# input3.net
KiCad netlist of a schematic drawn in Altium Designer
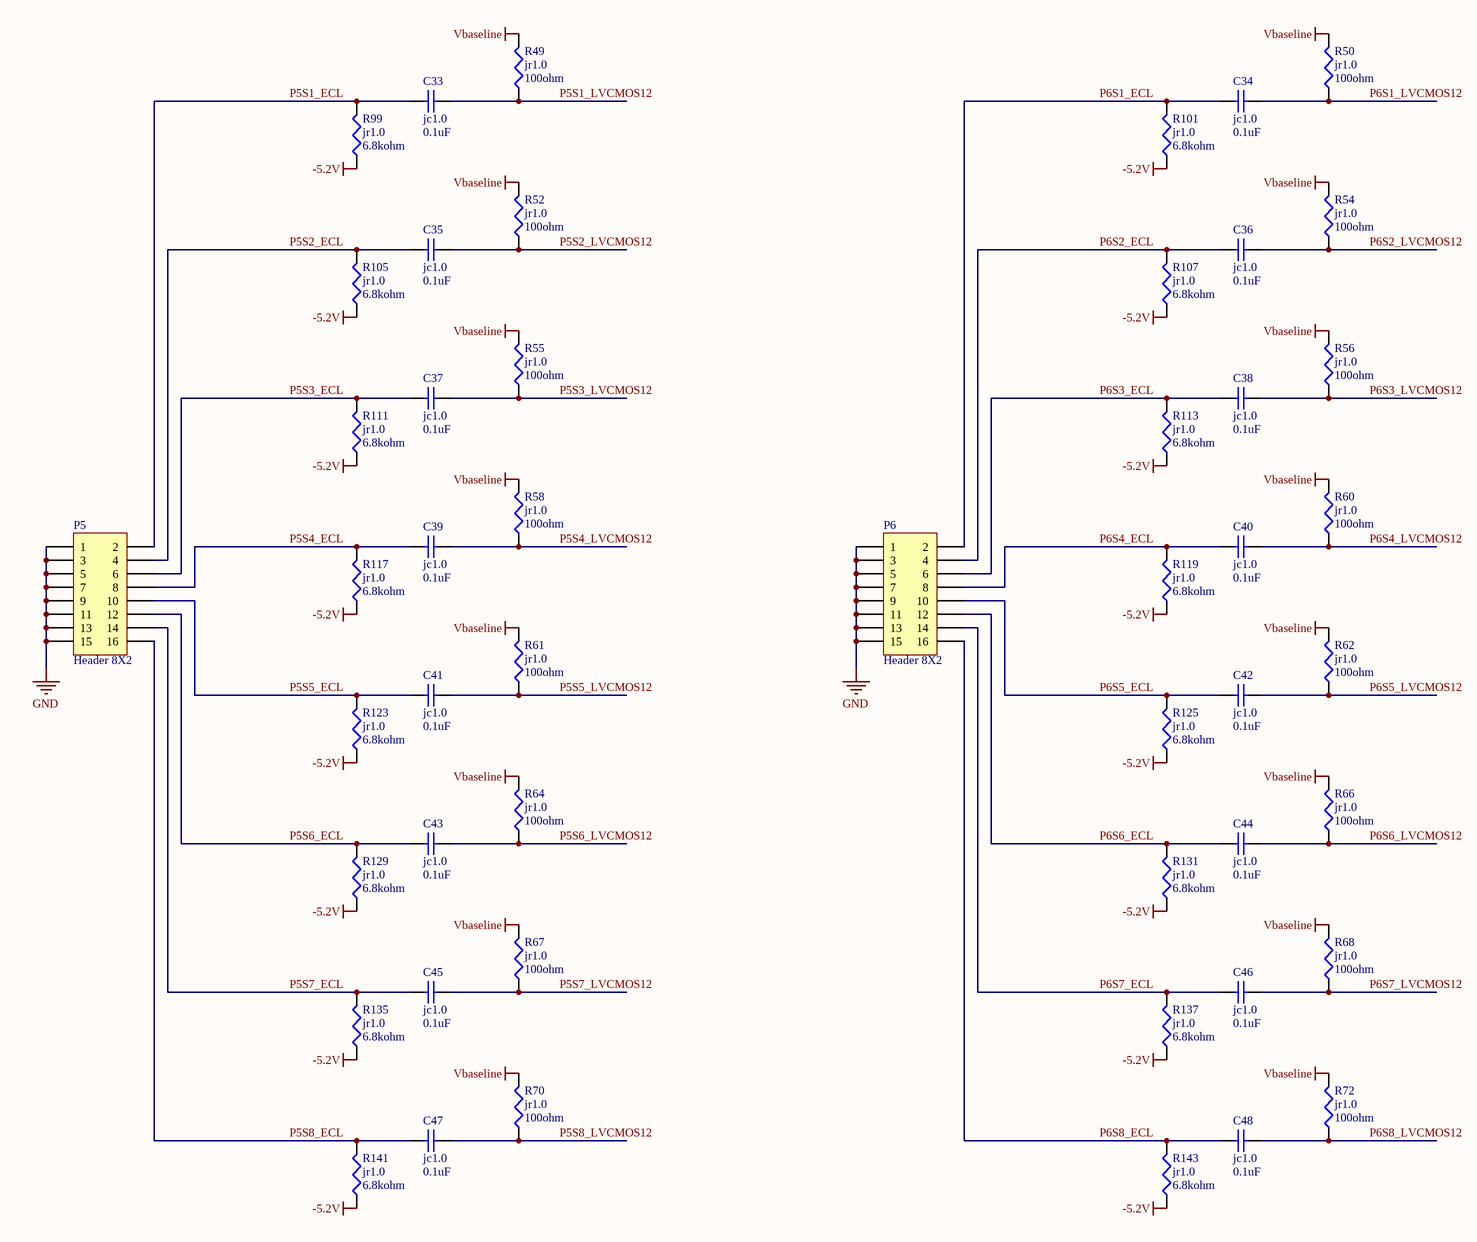
[diagram p0: input3.SchDoc]

(export (version "E")
  (design (tool "Eeschema 10.0.6"))
  (components
    (comp (ref "C33")
      (value "jc1.0")
      (footprint "0402")
      (description "Capacitor")
      (fields (field (name "ALTIUM_VALUE") "0.1uF") (field (name "PUBLISHER") "Altium Limited"))
      (libsource (lib "LIB01DXP2006SchLib") (part "Cap"))
    )
    (comp (ref "C34")
      (value "jc1.0")
      (footprint "0402")
      (description "Capacitor")
      (fields (field (name "ALTIUM_VALUE") "0.1uF") (field (name "PUBLISHER") "Altium Limited"))
      (libsource (lib "LIB01DXP2006SchLib") (part "Cap"))
    )
    (comp (ref "C35")
      (value "jc1.0")
      (footprint "0402")
      (description "Capacitor")
      (fields (field (name "ALTIUM_VALUE") "0.1uF") (field (name "PUBLISHER") "Altium Limited"))
      (libsource (lib "LIB01DXP2006SchLib") (part "Cap"))
    )
    (comp (ref "C36")
      (value "jc1.0")
      (footprint "0402")
      (description "Capacitor")
      (fields (field (name "ALTIUM_VALUE") "0.1uF") (field (name "PUBLISHER") "Altium Limited"))
      (libsource (lib "LIB01DXP2006SchLib") (part "Cap"))
    )
    (comp (ref "C37")
      (value "jc1.0")
      (footprint "0402")
      (description "Capacitor")
      (fields (field (name "ALTIUM_VALUE") "0.1uF") (field (name "PUBLISHER") "Altium Limited"))
      (libsource (lib "LIB01DXP2006SchLib") (part "Cap"))
    )
    (comp (ref "C38")
      (value "jc1.0")
      (footprint "0402")
      (description "Capacitor")
      (fields (field (name "ALTIUM_VALUE") "0.1uF") (field (name "PUBLISHER") "Altium Limited"))
      (libsource (lib "LIB01DXP2006SchLib") (part "Cap"))
    )
    (comp (ref "C39")
      (value "jc1.0")
      (footprint "0402")
      (description "Capacitor")
      (fields (field (name "ALTIUM_VALUE") "0.1uF") (field (name "PUBLISHER") "Altium Limited"))
      (libsource (lib "LIB01DXP2006SchLib") (part "Cap"))
    )
    (comp (ref "C40")
      (value "jc1.0")
      (footprint "0402")
      (description "Capacitor")
      (fields (field (name "ALTIUM_VALUE") "0.1uF") (field (name "PUBLISHER") "Altium Limited"))
      (libsource (lib "LIB01DXP2006SchLib") (part "Cap"))
    )
    (comp (ref "C41")
      (value "jc1.0")
      (footprint "0402")
      (description "Capacitor")
      (fields (field (name "ALTIUM_VALUE") "0.1uF") (field (name "PUBLISHER") "Altium Limited"))
      (libsource (lib "LIB01DXP2006SchLib") (part "Cap"))
    )
    (comp (ref "C42")
      (value "jc1.0")
      (footprint "0402")
      (description "Capacitor")
      (fields (field (name "ALTIUM_VALUE") "0.1uF") (field (name "PUBLISHER") "Altium Limited"))
      (libsource (lib "LIB01DXP2006SchLib") (part "Cap"))
    )
    (comp (ref "C43")
      (value "jc1.0")
      (footprint "0402")
      (description "Capacitor")
      (fields (field (name "ALTIUM_VALUE") "0.1uF") (field (name "PUBLISHER") "Altium Limited"))
      (libsource (lib "LIB01DXP2006SchLib") (part "Cap"))
    )
    (comp (ref "C44")
      (value "jc1.0")
      (footprint "0402")
      (description "Capacitor")
      (fields (field (name "ALTIUM_VALUE") "0.1uF") (field (name "PUBLISHER") "Altium Limited"))
      (libsource (lib "LIB01DXP2006SchLib") (part "Cap"))
    )
    (comp (ref "C45")
      (value "jc1.0")
      (footprint "0402")
      (description "Capacitor")
      (fields (field (name "ALTIUM_VALUE") "0.1uF") (field (name "PUBLISHER") "Altium Limited"))
      (libsource (lib "LIB01DXP2006SchLib") (part "Cap"))
    )
    (comp (ref "C46")
      (value "jc1.0")
      (footprint "0402")
      (description "Capacitor")
      (fields (field (name "ALTIUM_VALUE") "0.1uF") (field (name "PUBLISHER") "Altium Limited"))
      (libsource (lib "LIB01DXP2006SchLib") (part "Cap"))
    )
    (comp (ref "C47")
      (value "jc1.0")
      (footprint "0402")
      (description "Capacitor")
      (fields (field (name "ALTIUM_VALUE") "0.1uF") (field (name "PUBLISHER") "Altium Limited"))
      (libsource (lib "LIB01DXP2006SchLib") (part "Cap"))
    )
    (comp (ref "C48")
      (value "jc1.0")
      (footprint "0402")
      (description "Capacitor")
      (fields (field (name "ALTIUM_VALUE") "0.1uF") (field (name "PUBLISHER") "Altium Limited"))
      (libsource (lib "LIB01DXP2006SchLib") (part "Cap"))
    )
    (comp (ref "P5")
      (value "Header 8X2")
      (footprint "HDR2X8")
      (description "Header, 8-Pin, Dual row")
      (fields (field (name "PUBLISHER") "Altium Limited"))
      (libsource (lib "Miscellaneous Connectors") (part "Header 8X2"))
    )
    (comp (ref "P6")
      (value "Header 8X2")
      (footprint "HDR2X8")
      (description "Header, 8-Pin, Dual row")
      (fields (field (name "PUBLISHER") "Altium Limited"))
      (libsource (lib "Miscellaneous Connectors") (part "Header 8X2"))
    )
    (comp (ref "R49")
      (value "jr1.0")
      (footprint "0402")
      (description "Resistor")
      (fields (field (name "ALTIUM_VALUE") "100ohm") (field (name "PUBLISHER") "Altium Limited"))
      (libsource (lib "LIB01DXP2006SchLib") (part "Res"))
    )
    (comp (ref "R50")
      (value "jr1.0")
      (footprint "0402")
      (description "Resistor")
      (fields (field (name "ALTIUM_VALUE") "100ohm") (field (name "PUBLISHER") "Altium Limited"))
      (libsource (lib "LIB01DXP2006SchLib") (part "Res"))
    )
    (comp (ref "R52")
      (value "jr1.0")
      (footprint "0402")
      (description "Resistor")
      (fields (field (name "ALTIUM_VALUE") "100ohm") (field (name "PUBLISHER") "Altium Limited"))
      (libsource (lib "LIB01DXP2006SchLib") (part "Res"))
    )
    (comp (ref "R54")
      (value "jr1.0")
      (footprint "0402")
      (description "Resistor")
      (fields (field (name "ALTIUM_VALUE") "100ohm") (field (name "PUBLISHER") "Altium Limited"))
      (libsource (lib "LIB01DXP2006SchLib") (part "Res"))
    )
    (comp (ref "R55")
      (value "jr1.0")
      (footprint "0402")
      (description "Resistor")
      (fields (field (name "ALTIUM_VALUE") "100ohm") (field (name "PUBLISHER") "Altium Limited"))
      (libsource (lib "LIB01DXP2006SchLib") (part "Res"))
    )
    (comp (ref "R56")
      (value "jr1.0")
      (footprint "0402")
      (description "Resistor")
      (fields (field (name "ALTIUM_VALUE") "100ohm") (field (name "PUBLISHER") "Altium Limited"))
      (libsource (lib "LIB01DXP2006SchLib") (part "Res"))
    )
    (comp (ref "R58")
      (value "jr1.0")
      (footprint "0402")
      (description "Resistor")
      (fields (field (name "ALTIUM_VALUE") "100ohm") (field (name "PUBLISHER") "Altium Limited"))
      (libsource (lib "LIB01DXP2006SchLib") (part "Res"))
    )
    (comp (ref "R60")
      (value "jr1.0")
      (footprint "0402")
      (description "Resistor")
      (fields (field (name "ALTIUM_VALUE") "100ohm") (field (name "PUBLISHER") "Altium Limited"))
      (libsource (lib "LIB01DXP2006SchLib") (part "Res"))
    )
    (comp (ref "R61")
      (value "jr1.0")
      (footprint "0402")
      (description "Resistor")
      (fields (field (name "ALTIUM_VALUE") "100ohm") (field (name "PUBLISHER") "Altium Limited"))
      (libsource (lib "LIB01DXP2006SchLib") (part "Res"))
    )
    (comp (ref "R62")
      (value "jr1.0")
      (footprint "0402")
      (description "Resistor")
      (fields (field (name "ALTIUM_VALUE") "100ohm") (field (name "PUBLISHER") "Altium Limited"))
      (libsource (lib "LIB01DXP2006SchLib") (part "Res"))
    )
    (comp (ref "R64")
      (value "jr1.0")
      (footprint "0402")
      (description "Resistor")
      (fields (field (name "ALTIUM_VALUE") "100ohm") (field (name "PUBLISHER") "Altium Limited"))
      (libsource (lib "LIB01DXP2006SchLib") (part "Res"))
    )
    (comp (ref "R66")
      (value "jr1.0")
      (footprint "0402")
      (description "Resistor")
      (fields (field (name "ALTIUM_VALUE") "100ohm") (field (name "PUBLISHER") "Altium Limited"))
      (libsource (lib "LIB01DXP2006SchLib") (part "Res"))
    )
    (comp (ref "R67")
      (value "jr1.0")
      (footprint "0402")
      (description "Resistor")
      (fields (field (name "ALTIUM_VALUE") "100ohm") (field (name "PUBLISHER") "Altium Limited"))
      (libsource (lib "LIB01DXP2006SchLib") (part "Res"))
    )
    (comp (ref "R68")
      (value "jr1.0")
      (footprint "0402")
      (description "Resistor")
      (fields (field (name "ALTIUM_VALUE") "100ohm") (field (name "PUBLISHER") "Altium Limited"))
      (libsource (lib "LIB01DXP2006SchLib") (part "Res"))
    )
    (comp (ref "R70")
      (value "jr1.0")
      (footprint "0402")
      (description "Resistor")
      (fields (field (name "ALTIUM_VALUE") "100ohm") (field (name "PUBLISHER") "Altium Limited"))
      (libsource (lib "LIB01DXP2006SchLib") (part "Res"))
    )
    (comp (ref "R72")
      (value "jr1.0")
      (footprint "0402")
      (description "Resistor")
      (fields (field (name "ALTIUM_VALUE") "100ohm") (field (name "PUBLISHER") "Altium Limited"))
      (libsource (lib "LIB01DXP2006SchLib") (part "Res"))
    )
    (comp (ref "R99")
      (value "jr1.0")
      (footprint "0402")
      (description "Resistor")
      (fields (field (name "ALTIUM_VALUE") "6.8kohm") (field (name "PUBLISHER") "Altium Limited"))
      (libsource (lib "LIB01DXP2006SchLib") (part "Res"))
    )
    (comp (ref "R101")
      (value "jr1.0")
      (footprint "0402")
      (description "Resistor")
      (fields (field (name "ALTIUM_VALUE") "6.8kohm") (field (name "PUBLISHER") "Altium Limited"))
      (libsource (lib "LIB01DXP2006SchLib") (part "Res"))
    )
    (comp (ref "R105")
      (value "jr1.0")
      (footprint "0402")
      (description "Resistor")
      (fields (field (name "ALTIUM_VALUE") "6.8kohm") (field (name "PUBLISHER") "Altium Limited"))
      (libsource (lib "LIB01DXP2006SchLib") (part "Res"))
    )
    (comp (ref "R107")
      (value "jr1.0")
      (footprint "0402")
      (description "Resistor")
      (fields (field (name "ALTIUM_VALUE") "6.8kohm") (field (name "PUBLISHER") "Altium Limited"))
      (libsource (lib "LIB01DXP2006SchLib") (part "Res"))
    )
    (comp (ref "R111")
      (value "jr1.0")
      (footprint "0402")
      (description "Resistor")
      (fields (field (name "ALTIUM_VALUE") "6.8kohm") (field (name "PUBLISHER") "Altium Limited"))
      (libsource (lib "LIB01DXP2006SchLib") (part "Res"))
    )
    (comp (ref "R113")
      (value "jr1.0")
      (footprint "0402")
      (description "Resistor")
      (fields (field (name "ALTIUM_VALUE") "6.8kohm") (field (name "PUBLISHER") "Altium Limited"))
      (libsource (lib "LIB01DXP2006SchLib") (part "Res"))
    )
    (comp (ref "R117")
      (value "jr1.0")
      (footprint "0402")
      (description "Resistor")
      (fields (field (name "ALTIUM_VALUE") "6.8kohm") (field (name "PUBLISHER") "Altium Limited"))
      (libsource (lib "LIB01DXP2006SchLib") (part "Res"))
    )
    (comp (ref "R119")
      (value "jr1.0")
      (footprint "0402")
      (description "Resistor")
      (fields (field (name "ALTIUM_VALUE") "6.8kohm") (field (name "PUBLISHER") "Altium Limited"))
      (libsource (lib "LIB01DXP2006SchLib") (part "Res"))
    )
    (comp (ref "R123")
      (value "jr1.0")
      (footprint "0402")
      (description "Resistor")
      (fields (field (name "ALTIUM_VALUE") "6.8kohm") (field (name "PUBLISHER") "Altium Limited"))
      (libsource (lib "LIB01DXP2006SchLib") (part "Res"))
    )
    (comp (ref "R125")
      (value "jr1.0")
      (footprint "0402")
      (description "Resistor")
      (fields (field (name "ALTIUM_VALUE") "6.8kohm") (field (name "PUBLISHER") "Altium Limited"))
      (libsource (lib "LIB01DXP2006SchLib") (part "Res"))
    )
    (comp (ref "R129")
      (value "jr1.0")
      (footprint "0402")
      (description "Resistor")
      (fields (field (name "ALTIUM_VALUE") "6.8kohm") (field (name "PUBLISHER") "Altium Limited"))
      (libsource (lib "LIB01DXP2006SchLib") (part "Res"))
    )
    (comp (ref "R131")
      (value "jr1.0")
      (footprint "0402")
      (description "Resistor")
      (fields (field (name "ALTIUM_VALUE") "6.8kohm") (field (name "PUBLISHER") "Altium Limited"))
      (libsource (lib "LIB01DXP2006SchLib") (part "Res"))
    )
    (comp (ref "R135")
      (value "jr1.0")
      (footprint "0402")
      (description "Resistor")
      (fields (field (name "ALTIUM_VALUE") "6.8kohm") (field (name "PUBLISHER") "Altium Limited"))
      (libsource (lib "LIB01DXP2006SchLib") (part "Res"))
    )
    (comp (ref "R137")
      (value "jr1.0")
      (footprint "0402")
      (description "Resistor")
      (fields (field (name "ALTIUM_VALUE") "6.8kohm") (field (name "PUBLISHER") "Altium Limited"))
      (libsource (lib "LIB01DXP2006SchLib") (part "Res"))
    )
    (comp (ref "R141")
      (value "jr1.0")
      (footprint "0402")
      (description "Resistor")
      (fields (field (name "ALTIUM_VALUE") "6.8kohm") (field (name "PUBLISHER") "Altium Limited"))
      (libsource (lib "LIB01DXP2006SchLib") (part "Res"))
    )
    (comp (ref "R143")
      (value "jr1.0")
      (footprint "0402")
      (description "Resistor")
      (fields (field (name "ALTIUM_VALUE") "6.8kohm") (field (name "PUBLISHER") "Altium Limited"))
      (libsource (lib "LIB01DXP2006SchLib") (part "Res"))
    )
  )
  (nets
    (net (code "1") (name "-5.2V") (class "Default")
      (node (ref "R101") (pin "1") (pinfunction "1_1") (pintype "passive"))
      (node (ref "R105") (pin "1") (pinfunction "1_1") (pintype "passive"))
      (node (ref "R107") (pin "1") (pinfunction "1_1") (pintype "passive"))
      (node (ref "R111") (pin "1") (pinfunction "1_1") (pintype "passive"))
      (node (ref "R113") (pin "1") (pinfunction "1_1") (pintype "passive"))
      (node (ref "R117") (pin "1") (pinfunction "1_1") (pintype "passive"))
      (node (ref "R119") (pin "1") (pinfunction "1_1") (pintype "passive"))
      (node (ref "R123") (pin "1") (pinfunction "1_1") (pintype "passive"))
      (node (ref "R125") (pin "1") (pinfunction "1_1") (pintype "passive"))
      (node (ref "R129") (pin "1") (pinfunction "1_1") (pintype "passive"))
      (node (ref "R131") (pin "1") (pinfunction "1_1") (pintype "passive"))
      (node (ref "R135") (pin "1") (pinfunction "1_1") (pintype "passive"))
      (node (ref "R137") (pin "1") (pinfunction "1_1") (pintype "passive"))
      (node (ref "R141") (pin "1") (pinfunction "1_1") (pintype "passive"))
      (node (ref "R143") (pin "1") (pinfunction "1_1") (pintype "passive"))
      (node (ref "R99") (pin "1") (pinfunction "1_1") (pintype "passive"))
    )
    (net (code "2") (name "/P5S1_ECL") (class "Default")
      (node (ref "C33") (pin "1") (pinfunction "1_1") (pintype "passive"))
      (node (ref "P5") (pin "2") (pinfunction "2_2") (pintype "passive"))
      (node (ref "R99") (pin "2") (pinfunction "2_2") (pintype "passive"))
    )
    (net (code "3") (name "/P5S1_LVCMOS12") (class "Default")
      (node (ref "C33") (pin "2") (pinfunction "2_2") (pintype "passive"))
      (node (ref "R49") (pin "1") (pinfunction "1_1") (pintype "passive"))
    )
    (net (code "4") (name "/P5S2_ECL") (class "Default")
      (node (ref "C35") (pin "1") (pinfunction "1_1") (pintype "passive"))
      (node (ref "P5") (pin "4") (pinfunction "4_4") (pintype "passive"))
      (node (ref "R105") (pin "2") (pinfunction "2_2") (pintype "passive"))
    )
    (net (code "5") (name "/P5S2_LVCMOS12") (class "Default")
      (node (ref "C35") (pin "2") (pinfunction "2_2") (pintype "passive"))
      (node (ref "R52") (pin "1") (pinfunction "1_1") (pintype "passive"))
    )
    (net (code "6") (name "/P5S3_ECL") (class "Default")
      (node (ref "C37") (pin "1") (pinfunction "1_1") (pintype "passive"))
      (node (ref "P5") (pin "6") (pinfunction "6_6") (pintype "passive"))
      (node (ref "R111") (pin "2") (pinfunction "2_2") (pintype "passive"))
    )
    (net (code "7") (name "/P5S3_LVCMOS12") (class "Default")
      (node (ref "C37") (pin "2") (pinfunction "2_2") (pintype "passive"))
      (node (ref "R55") (pin "1") (pinfunction "1_1") (pintype "passive"))
    )
    (net (code "8") (name "/P5S4_ECL") (class "Default")
      (node (ref "C39") (pin "1") (pinfunction "1_1") (pintype "passive"))
      (node (ref "P5") (pin "8") (pinfunction "8_8") (pintype "passive"))
      (node (ref "R117") (pin "2") (pinfunction "2_2") (pintype "passive"))
    )
    (net (code "9") (name "/P5S4_LVCMOS12") (class "Default")
      (node (ref "C39") (pin "2") (pinfunction "2_2") (pintype "passive"))
      (node (ref "R58") (pin "1") (pinfunction "1_1") (pintype "passive"))
    )
    (net (code "10") (name "/P5S5_ECL") (class "Default")
      (node (ref "C41") (pin "1") (pinfunction "1_1") (pintype "passive"))
      (node (ref "P5") (pin "10") (pinfunction "10_10") (pintype "passive"))
      (node (ref "R123") (pin "2") (pinfunction "2_2") (pintype "passive"))
    )
    (net (code "11") (name "/P5S5_LVCMOS12") (class "Default")
      (node (ref "C41") (pin "2") (pinfunction "2_2") (pintype "passive"))
      (node (ref "R61") (pin "1") (pinfunction "1_1") (pintype "passive"))
    )
    (net (code "12") (name "/P5S6_ECL") (class "Default")
      (node (ref "C43") (pin "1") (pinfunction "1_1") (pintype "passive"))
      (node (ref "P5") (pin "12") (pinfunction "12_12") (pintype "passive"))
      (node (ref "R129") (pin "2") (pinfunction "2_2") (pintype "passive"))
    )
    (net (code "13") (name "/P5S6_LVCMOS12") (class "Default")
      (node (ref "C43") (pin "2") (pinfunction "2_2") (pintype "passive"))
      (node (ref "R64") (pin "1") (pinfunction "1_1") (pintype "passive"))
    )
    (net (code "14") (name "/P5S7_ECL") (class "Default")
      (node (ref "C45") (pin "1") (pinfunction "1_1") (pintype "passive"))
      (node (ref "P5") (pin "14") (pinfunction "14_14") (pintype "passive"))
      (node (ref "R135") (pin "2") (pinfunction "2_2") (pintype "passive"))
    )
    (net (code "15") (name "/P5S7_LVCMOS12") (class "Default")
      (node (ref "C45") (pin "2") (pinfunction "2_2") (pintype "passive"))
      (node (ref "R67") (pin "1") (pinfunction "1_1") (pintype "passive"))
    )
    (net (code "16") (name "/P5S8_ECL") (class "Default")
      (node (ref "C47") (pin "1") (pinfunction "1_1") (pintype "passive"))
      (node (ref "P5") (pin "16") (pinfunction "16_16") (pintype "passive"))
      (node (ref "R141") (pin "2") (pinfunction "2_2") (pintype "passive"))
    )
    (net (code "17") (name "/P5S8_LVCMOS12") (class "Default")
      (node (ref "C47") (pin "2") (pinfunction "2_2") (pintype "passive"))
      (node (ref "R70") (pin "1") (pinfunction "1_1") (pintype "passive"))
    )
    (net (code "18") (name "/P6S1_ECL") (class "Default")
      (node (ref "C34") (pin "1") (pinfunction "1_1") (pintype "passive"))
      (node (ref "P6") (pin "2") (pinfunction "2_2") (pintype "passive"))
      (node (ref "R101") (pin "2") (pinfunction "2_2") (pintype "passive"))
    )
    (net (code "19") (name "/P6S1_LVCMOS12") (class "Default")
      (node (ref "C34") (pin "2") (pinfunction "2_2") (pintype "passive"))
      (node (ref "R50") (pin "1") (pinfunction "1_1") (pintype "passive"))
    )
    (net (code "20") (name "/P6S2_ECL") (class "Default")
      (node (ref "C36") (pin "1") (pinfunction "1_1") (pintype "passive"))
      (node (ref "P6") (pin "4") (pinfunction "4_4") (pintype "passive"))
      (node (ref "R107") (pin "2") (pinfunction "2_2") (pintype "passive"))
    )
    (net (code "21") (name "/P6S2_LVCMOS12") (class "Default")
      (node (ref "C36") (pin "2") (pinfunction "2_2") (pintype "passive"))
      (node (ref "R54") (pin "1") (pinfunction "1_1") (pintype "passive"))
    )
    (net (code "22") (name "/P6S3_ECL") (class "Default")
      (node (ref "C38") (pin "1") (pinfunction "1_1") (pintype "passive"))
      (node (ref "P6") (pin "6") (pinfunction "6_6") (pintype "passive"))
      (node (ref "R113") (pin "2") (pinfunction "2_2") (pintype "passive"))
    )
    (net (code "23") (name "/P6S3_LVCMOS12") (class "Default")
      (node (ref "C38") (pin "2") (pinfunction "2_2") (pintype "passive"))
      (node (ref "R56") (pin "1") (pinfunction "1_1") (pintype "passive"))
    )
    (net (code "24") (name "/P6S4_ECL") (class "Default")
      (node (ref "C40") (pin "1") (pinfunction "1_1") (pintype "passive"))
      (node (ref "P6") (pin "8") (pinfunction "8_8") (pintype "passive"))
      (node (ref "R119") (pin "2") (pinfunction "2_2") (pintype "passive"))
    )
    (net (code "25") (name "/P6S4_LVCMOS12") (class "Default")
      (node (ref "C40") (pin "2") (pinfunction "2_2") (pintype "passive"))
      (node (ref "R60") (pin "1") (pinfunction "1_1") (pintype "passive"))
    )
    (net (code "26") (name "/P6S5_ECL") (class "Default")
      (node (ref "C42") (pin "1") (pinfunction "1_1") (pintype "passive"))
      (node (ref "P6") (pin "10") (pinfunction "10_10") (pintype "passive"))
      (node (ref "R125") (pin "2") (pinfunction "2_2") (pintype "passive"))
    )
    (net (code "27") (name "/P6S5_LVCMOS12") (class "Default")
      (node (ref "C42") (pin "2") (pinfunction "2_2") (pintype "passive"))
      (node (ref "R62") (pin "1") (pinfunction "1_1") (pintype "passive"))
    )
    (net (code "28") (name "/P6S6_ECL") (class "Default")
      (node (ref "C44") (pin "1") (pinfunction "1_1") (pintype "passive"))
      (node (ref "P6") (pin "12") (pinfunction "12_12") (pintype "passive"))
      (node (ref "R131") (pin "2") (pinfunction "2_2") (pintype "passive"))
    )
    (net (code "29") (name "/P6S6_LVCMOS12") (class "Default")
      (node (ref "C44") (pin "2") (pinfunction "2_2") (pintype "passive"))
      (node (ref "R66") (pin "1") (pinfunction "1_1") (pintype "passive"))
    )
    (net (code "30") (name "/P6S7_ECL") (class "Default")
      (node (ref "C46") (pin "1") (pinfunction "1_1") (pintype "passive"))
      (node (ref "P6") (pin "14") (pinfunction "14_14") (pintype "passive"))
      (node (ref "R137") (pin "2") (pinfunction "2_2") (pintype "passive"))
    )
    (net (code "31") (name "/P6S7_LVCMOS12") (class "Default")
      (node (ref "C46") (pin "2") (pinfunction "2_2") (pintype "passive"))
      (node (ref "R68") (pin "1") (pinfunction "1_1") (pintype "passive"))
    )
    (net (code "32") (name "/P6S8_ECL") (class "Default")
      (node (ref "C48") (pin "1") (pinfunction "1_1") (pintype "passive"))
      (node (ref "P6") (pin "16") (pinfunction "16_16") (pintype "passive"))
      (node (ref "R143") (pin "2") (pinfunction "2_2") (pintype "passive"))
    )
    (net (code "33") (name "/P6S8_LVCMOS12") (class "Default")
      (node (ref "C48") (pin "2") (pinfunction "2_2") (pintype "passive"))
      (node (ref "R72") (pin "1") (pinfunction "1_1") (pintype "passive"))
    )
    (net (code "34") (name "GND") (class "Default")
      (node (ref "P5") (pin "1") (pinfunction "1_1") (pintype "passive"))
      (node (ref "P5") (pin "11") (pinfunction "11_11") (pintype "passive"))
      (node (ref "P5") (pin "13") (pinfunction "13_13") (pintype "passive"))
      (node (ref "P5") (pin "15") (pinfunction "15_15") (pintype "passive"))
      (node (ref "P5") (pin "3") (pinfunction "3_3") (pintype "passive"))
      (node (ref "P5") (pin "5") (pinfunction "5_5") (pintype "passive"))
      (node (ref "P5") (pin "7") (pinfunction "7_7") (pintype "passive"))
      (node (ref "P5") (pin "9") (pinfunction "9_9") (pintype "passive"))
      (node (ref "P6") (pin "1") (pinfunction "1_1") (pintype "passive"))
      (node (ref "P6") (pin "11") (pinfunction "11_11") (pintype "passive"))
      (node (ref "P6") (pin "13") (pinfunction "13_13") (pintype "passive"))
      (node (ref "P6") (pin "15") (pinfunction "15_15") (pintype "passive"))
      (node (ref "P6") (pin "3") (pinfunction "3_3") (pintype "passive"))
      (node (ref "P6") (pin "5") (pinfunction "5_5") (pintype "passive"))
      (node (ref "P6") (pin "7") (pinfunction "7_7") (pintype "passive"))
      (node (ref "P6") (pin "9") (pinfunction "9_9") (pintype "passive"))
    )
    (net (code "35") (name "Vbaseline") (class "Default")
      (node (ref "R49") (pin "2") (pinfunction "2_2") (pintype "passive"))
      (node (ref "R50") (pin "2") (pinfunction "2_2") (pintype "passive"))
      (node (ref "R52") (pin "2") (pinfunction "2_2") (pintype "passive"))
      (node (ref "R54") (pin "2") (pinfunction "2_2") (pintype "passive"))
      (node (ref "R55") (pin "2") (pinfunction "2_2") (pintype "passive"))
      (node (ref "R56") (pin "2") (pinfunction "2_2") (pintype "passive"))
      (node (ref "R58") (pin "2") (pinfunction "2_2") (pintype "passive"))
      (node (ref "R60") (pin "2") (pinfunction "2_2") (pintype "passive"))
      (node (ref "R61") (pin "2") (pinfunction "2_2") (pintype "passive"))
      (node (ref "R62") (pin "2") (pinfunction "2_2") (pintype "passive"))
      (node (ref "R64") (pin "2") (pinfunction "2_2") (pintype "passive"))
      (node (ref "R66") (pin "2") (pinfunction "2_2") (pintype "passive"))
      (node (ref "R67") (pin "2") (pinfunction "2_2") (pintype "passive"))
      (node (ref "R68") (pin "2") (pinfunction "2_2") (pintype "passive"))
      (node (ref "R70") (pin "2") (pinfunction "2_2") (pintype "passive"))
      (node (ref "R72") (pin "2") (pinfunction "2_2") (pintype "passive"))
    )
  )
)
